# relay_sch.net
KiCad netlist of a schematic drawn in EAGLE
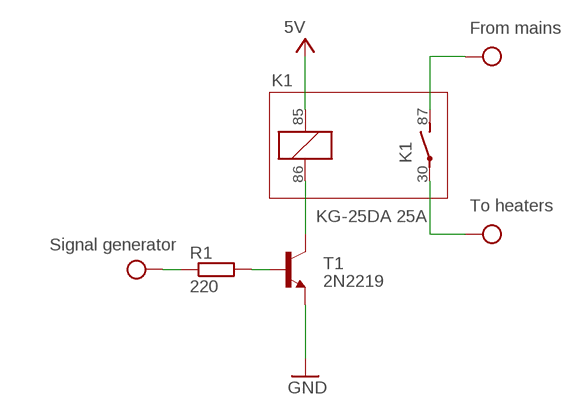
[diagram p0: schematic, sheet 1]

(export (version "E")
  (design (tool "Eeschema 10.0.6"))
  (components
    (comp (ref "K1")
      (value "KG-25DA 25A")
      (footprint "eagle-import:CM")
      (fields (field (name "MF") "AROMAT/ MATSUSHITA") (field (name "MPN") "CM1AF-P-12V"))
      (libsource (lib "eagle-import") (part "CM1AF-P-12V"))
    )
    (comp (ref "R1")
      (value "220")
      (footprint "eagle-import:0204V")
      (libsource (lib "eagle-import") (part "R-EU_0204/2V"))
    )
    (comp (ref "T1")
      (value "2N2219")
      (footprint "eagle-import:TO5")
      (libsource (lib "eagle-import") (part "2N2219"))
    )
  )
  (nets
    (net (code "1") (name "5V") (class "Default")
      (node (ref "K1") (pin "30") (pinfunction "P_30") (pintype "passive"))
      (node (ref "K1") (pin "85") (pinfunction "1_85") (pintype "passive"))
      (node (ref "K1") (pin "87") (pinfunction "S_87") (pintype "passive"))
      (node (ref "R1") (pin "1") (pinfunction "1_1") (pintype "passive"))
    )
    (net (code "2") (name "GND") (class "Default")
      (node (ref "T1") (pin "1") (pinfunction "E_1") (pintype "passive"))
    )
    (net (code "3") (name "Net-(K1A-2)") (class "Default")
      (node (ref "K1") (pin "86") (pinfunction "2_86") (pintype "passive"))
      (node (ref "T1") (pin "3") (pinfunction "C_3") (pintype "passive"))
    )
    (net (code "4") (name "Net-(T1-B)") (class "Default")
      (node (ref "R1") (pin "2") (pinfunction "2_2") (pintype "passive"))
      (node (ref "T1") (pin "2") (pinfunction "B_2") (pintype "passive"))
    )
  )
)
